# DSO_Counters.net
KiCad netlist of a schematic drawn in Altium Designer
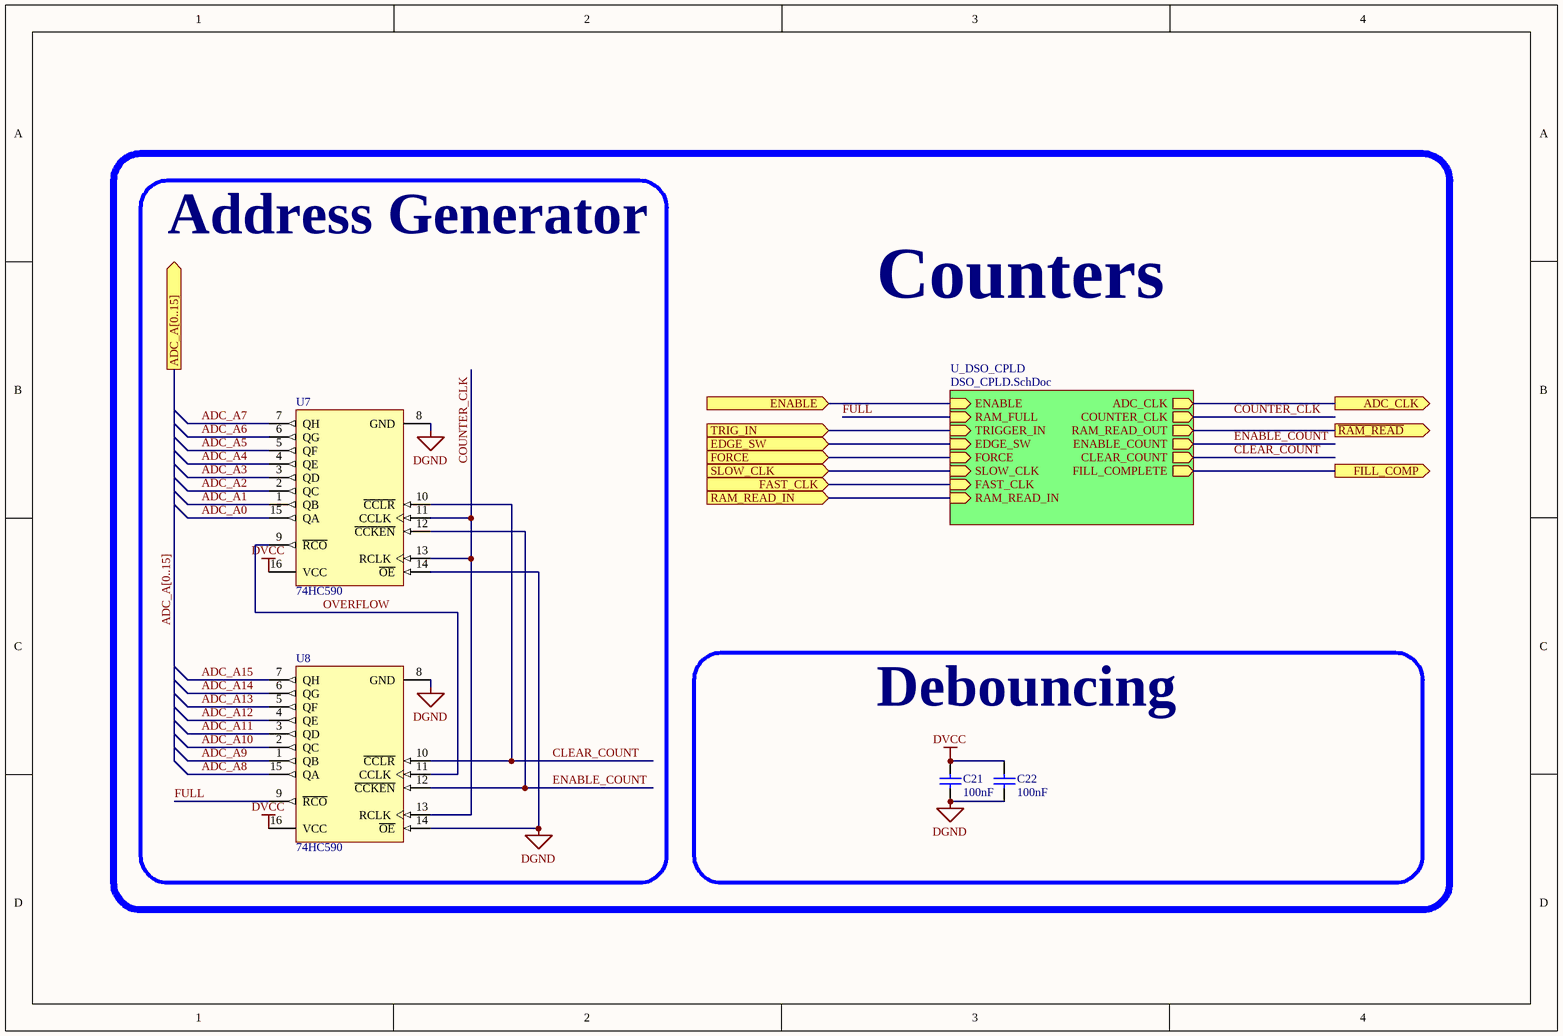
[diagram p0: DSO_Counters.SchDoc]

(export (version "E")
  (design (tool "Eeschema 10.0.6"))
  (components
    (comp (ref "C21")
      (value "100nF")
      (footprint "0805C")
      (description "Capacitor")
      (fields (field (name "REVIEWED BY") "RM - 2018/08/05"))
      (libsource (lib "DSO") (part "C"))
    )
    (comp (ref "C22")
      (value "100nF")
      (footprint "0805C")
      (description "Capacitor")
      (fields (field (name "REVIEWED BY") "RM - 2018/08/05"))
      (libsource (lib "DSO") (part "C"))
    )
    (comp (ref "U7")
      (value "74HC590")
      (footprint "SOIC-16")
      (description "8-Bit Binary Counter Register")
      (fields (field (name "REVIEWED BY") "RM - 2018/08/05"))
      (libsource (lib "DSO") (part "74HC590"))
    )
    (comp (ref "U8")
      (value "74HC590")
      (footprint "SOIC-16")
      (description "8-Bit Binary Counter Register")
      (fields (field (name "REVIEWED BY") "RM - 2018/08/05"))
      (libsource (lib "DSO") (part "74HC590"))
    )
  )
  (nets
    (net (code "1") (name "/ADC_A0") (class "Default")
      (node (ref "U7") (pin "15") (pinfunction "QA_15") (pintype "output"))
    )
    (net (code "2") (name "/ADC_A1") (class "Default")
      (node (ref "U7") (pin "1") (pinfunction "QB_1") (pintype "output"))
    )
    (net (code "3") (name "/ADC_A2") (class "Default")
      (node (ref "U7") (pin "2") (pinfunction "QC_2") (pintype "output"))
    )
    (net (code "4") (name "/ADC_A3") (class "Default")
      (node (ref "U7") (pin "3") (pinfunction "QD_3") (pintype "output"))
    )
    (net (code "5") (name "/ADC_A4") (class "Default")
      (node (ref "U7") (pin "4") (pinfunction "QE_4") (pintype "output"))
    )
    (net (code "6") (name "/ADC_A5") (class "Default")
      (node (ref "U7") (pin "5") (pinfunction "QF_5") (pintype "output"))
    )
    (net (code "7") (name "/ADC_A6") (class "Default")
      (node (ref "U7") (pin "6") (pinfunction "QG_6") (pintype "output"))
    )
    (net (code "8") (name "/ADC_A7") (class "Default")
      (node (ref "U7") (pin "7") (pinfunction "QH_7") (pintype "output"))
    )
    (net (code "9") (name "/ADC_A8") (class "Default")
      (node (ref "U8") (pin "15") (pinfunction "QA_15") (pintype "output"))
    )
    (net (code "10") (name "/ADC_A9") (class "Default")
      (node (ref "U8") (pin "1") (pinfunction "QB_1") (pintype "output"))
    )
    (net (code "11") (name "/ADC_A10") (class "Default")
      (node (ref "U8") (pin "2") (pinfunction "QC_2") (pintype "output"))
    )
    (net (code "12") (name "/ADC_A11") (class "Default")
      (node (ref "U8") (pin "3") (pinfunction "QD_3") (pintype "output"))
    )
    (net (code "13") (name "/ADC_A12") (class "Default")
      (node (ref "U8") (pin "4") (pinfunction "QE_4") (pintype "output"))
    )
    (net (code "14") (name "/ADC_A13") (class "Default")
      (node (ref "U8") (pin "5") (pinfunction "QF_5") (pintype "output"))
    )
    (net (code "15") (name "/ADC_A14") (class "Default")
      (node (ref "U8") (pin "6") (pinfunction "QG_6") (pintype "output"))
    )
    (net (code "16") (name "/ADC_A15") (class "Default")
      (node (ref "U8") (pin "7") (pinfunction "QH_7") (pintype "output"))
    )
    (net (code "19") (name "/CLEAR_COUNT") (class "Default")
      (node (ref "U7") (pin "10") (pinfunction "~{CCLR}_10") (pintype "input"))
      (node (ref "U8") (pin "10") (pinfunction "~{CCLR}_10") (pintype "input"))
    )
    (net (code "20") (name "/COUNTER_CLK") (class "Default")
      (node (ref "U7") (pin "11") (pinfunction "CCLK_11") (pintype "input"))
      (node (ref "U7") (pin "13") (pinfunction "RCLK_13") (pintype "input"))
      (node (ref "U8") (pin "13") (pinfunction "RCLK_13") (pintype "input"))
    )
    (net (code "23") (name "/ENABLE_COUNT") (class "Default")
      (node (ref "U7") (pin "12") (pinfunction "~{CCKEN}_12") (pintype "input"))
      (node (ref "U8") (pin "12") (pinfunction "~{CCKEN}_12") (pintype "input"))
    )
    (net (code "27") (name "/FULL") (class "Default")
      (node (ref "U8") (pin "9") (pinfunction "~{RCO}_9") (pintype "output"))
    )
    (net (code "28") (name "/OVERFLOW") (class "Default")
      (node (ref "U7") (pin "9") (pinfunction "~{RCO}_9") (pintype "output"))
      (node (ref "U8") (pin "11") (pinfunction "CCLK_11") (pintype "input"))
    )
    (net (code "33") (name "DGND") (class "Default")
      (node (ref "C21") (pin "2") (pinfunction "2_2") (pintype "passive"))
      (node (ref "C22") (pin "2") (pinfunction "2_2") (pintype "passive"))
      (node (ref "U7") (pin "14") (pinfunction "~{OE}_14") (pintype "input"))
      (node (ref "U7") (pin "8") (pinfunction "GND_8") (pintype "power_in"))
      (node (ref "U8") (pin "14") (pinfunction "~{OE}_14") (pintype "input"))
      (node (ref "U8") (pin "8") (pinfunction "GND_8") (pintype "power_in"))
    )
    (net (code "34") (name "DVCC") (class "Default")
      (node (ref "C21") (pin "1") (pinfunction "1_1") (pintype "passive"))
      (node (ref "C22") (pin "1") (pinfunction "1_1") (pintype "passive"))
      (node (ref "U7") (pin "16") (pinfunction "VCC_16") (pintype "power_in"))
      (node (ref "U8") (pin "16") (pinfunction "VCC_16") (pintype "power_in"))
    )
  )
)
